# M_I_ext_sound_usb.net
KiCad netlist of a schematic drawn in EAGLE
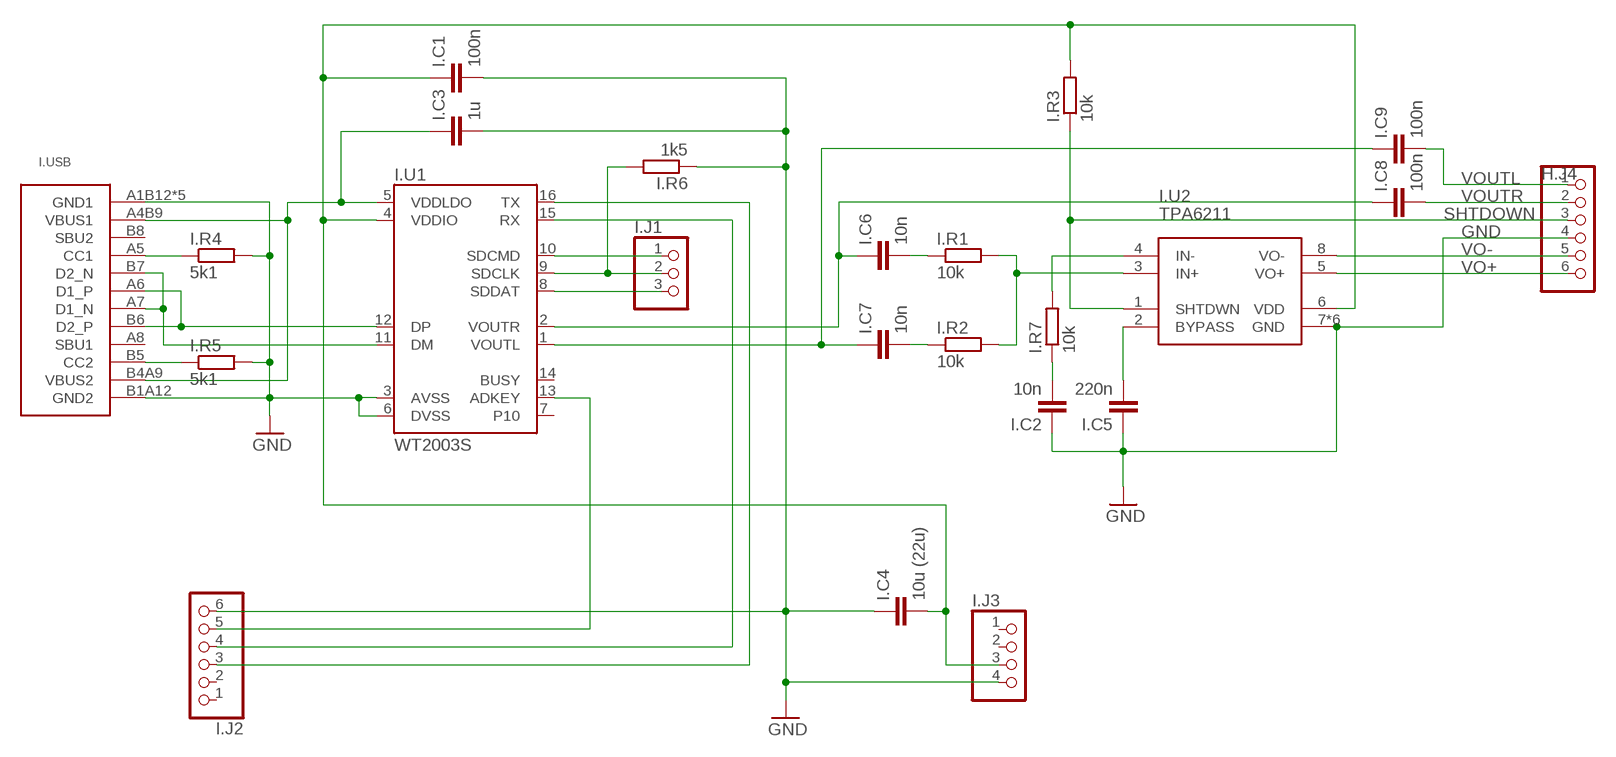
[diagram p0: schematic, sheet 1]

(export (version "E")
  (design (tool "Eeschema 10.0.6"))
  (components
    (comp (ref "H.J4")
      (value "PINHD-1X6")
      (footprint "eagle-import:1X06")
      (libsource (lib "eagle-import") (part "PINHD-1X6"))
    )
    (comp (ref "I.C1")
      (value "100n")
      (footprint "eagle-import:C0603")
      (libsource (lib "eagle-import") (part "C-EUC0603"))
    )
    (comp (ref "I.C2")
      (value "10n")
      (footprint "eagle-import:C0603")
      (libsource (lib "eagle-import") (part "C-EUC0603"))
    )
    (comp (ref "I.C3")
      (value "1u")
      (footprint "eagle-import:C0603")
      (libsource (lib "eagle-import") (part "C-EUC0603"))
    )
    (comp (ref "I.C4")
      (value "10u (22u)")
      (footprint "eagle-import:C0805")
      (libsource (lib "eagle-import") (part "C-EUC0805"))
    )
    (comp (ref "I.C5")
      (value "220n")
      (footprint "eagle-import:C0603")
      (libsource (lib "eagle-import") (part "C-EUC0603"))
    )
    (comp (ref "I.C6")
      (value "10n")
      (footprint "eagle-import:C0603")
      (libsource (lib "eagle-import") (part "C-EUC0603"))
    )
    (comp (ref "I.C7")
      (value "10n")
      (footprint "eagle-import:C0603")
      (libsource (lib "eagle-import") (part "C-EUC0603"))
    )
    (comp (ref "I.C8")
      (value "100n")
      (footprint "eagle-import:C0603")
      (libsource (lib "eagle-import") (part "C-EUC0603"))
    )
    (comp (ref "I.C9")
      (value "100n")
      (footprint "eagle-import:C0603")
      (libsource (lib "eagle-import") (part "C-EUC0603"))
    )
    (comp (ref "I.J1")
      (value "PINHD-1X3")
      (footprint "eagle-import:1X03")
      (libsource (lib "eagle-import") (part "PINHD-1X3"))
    )
    (comp (ref "I.J2")
      (value "PINHD-1X6")
      (footprint "eagle-import:1X06")
      (libsource (lib "eagle-import") (part "PINHD-1X6"))
    )
    (comp (ref "I.J3")
      (value "PINHD-1X4")
      (footprint "eagle-import:1X04")
      (libsource (lib "eagle-import") (part "PINHD-1X4"))
    )
    (comp (ref "I.R1")
      (value "10k")
      (footprint "eagle-import:R0603")
      (libsource (lib "eagle-import") (part "R-EU_R0603"))
    )
    (comp (ref "I.R2")
      (value "10k")
      (footprint "eagle-import:R0603")
      (libsource (lib "eagle-import") (part "R-EU_R0603"))
    )
    (comp (ref "I.R3")
      (value "10k")
      (footprint "eagle-import:R0603")
      (libsource (lib "eagle-import") (part "R-EU_R0603"))
    )
    (comp (ref "I.R4")
      (value "5k1")
      (footprint "eagle-import:R0603")
      (libsource (lib "eagle-import") (part "R-EU_R0603"))
    )
    (comp (ref "I.R5")
      (value "5k1")
      (footprint "eagle-import:R0603")
      (libsource (lib "eagle-import") (part "R-EU_R0603"))
    )
    (comp (ref "I.R6")
      (value "1k5")
      (footprint "eagle-import:R0603")
      (libsource (lib "eagle-import") (part "R-EU_R0603"))
    )
    (comp (ref "I.R7")
      (value "10k")
      (footprint "eagle-import:R0603")
      (libsource (lib "eagle-import") (part "R-EU_R0603"))
    )
    (comp (ref "I.U1")
      (value "WT2003S")
      (footprint "eagle-import:SO16")
      (libsource (lib "eagle-import") (part "WT2003S"))
    )
    (comp (ref "I.U2")
      (value "TPA6211")
      (footprint "eagle-import:MSOP-POWERPAD-8")
      (libsource (lib "eagle-import") (part "TPA6211"))
    )
    (comp (ref "I.USB")
      (value "USB-C")
      (footprint "eagle-import:USB-C")
      (libsource (lib "eagle-import") (part "USB-C"))
    )
  )
  (nets
    (net (code "1") (name "/SHTDOWN") (class "Default")
      (node (ref "H.J4") (pin "3") (pinfunction "3_3") (pintype "passive"))
      (node (ref "I.R3") (pin "1") (pinfunction "1_1") (pintype "passive"))
      (node (ref "I.U2") (pin "1") (pinfunction "SHTDWN_1") (pintype "bidirectional"))
    )
    (net (code "2") (name "/VO+") (class "Default")
      (node (ref "H.J4") (pin "6") (pinfunction "6_6") (pintype "passive"))
      (node (ref "I.U2") (pin "5") (pinfunction "VO+_5") (pintype "bidirectional"))
    )
    (net (code "3") (name "/VO-") (class "Default")
      (node (ref "H.J4") (pin "5") (pinfunction "5_5") (pintype "passive"))
      (node (ref "I.U2") (pin "8") (pinfunction "VO-_8") (pintype "bidirectional"))
    )
    (net (code "4") (name "/VOUTL") (class "Default")
      (node (ref "H.J4") (pin "1") (pinfunction "1_1") (pintype "passive"))
      (node (ref "I.C9") (pin "2") (pinfunction "2_2") (pintype "passive"))
    )
    (net (code "5") (name "/VOUTR") (class "Default")
      (node (ref "H.J4") (pin "2") (pinfunction "2_2") (pintype "passive"))
      (node (ref "I.C8") (pin "2") (pinfunction "2_2") (pintype "passive"))
    )
    (net (code "6") (name "GND") (class "Default")
      (node (ref "H.J4") (pin "4") (pinfunction "4_4") (pintype "passive"))
      (node (ref "I.C1") (pin "2") (pinfunction "2_2") (pintype "passive"))
      (node (ref "I.C2") (pin "1") (pinfunction "1_1") (pintype "passive"))
      (node (ref "I.C3") (pin "2") (pinfunction "2_2") (pintype "passive"))
      (node (ref "I.C4") (pin "1") (pinfunction "1_1") (pintype "passive"))
      (node (ref "I.C5") (pin "1") (pinfunction "1_1") (pintype "passive"))
      (node (ref "I.J2") (pin "6") (pinfunction "6_6") (pintype "passive"))
      (node (ref "I.J3") (pin "4") (pinfunction "4_4") (pintype "passive"))
      (node (ref "I.R4") (pin "2") (pinfunction "2_2") (pintype "passive"))
      (node (ref "I.R5") (pin "2") (pinfunction "2_2") (pintype "passive"))
      (node (ref "I.R6") (pin "1") (pinfunction "1_1") (pintype "passive"))
      (node (ref "I.U1") (pin "3") (pinfunction "AVSS_3") (pintype "bidirectional"))
      (node (ref "I.U1") (pin "6") (pinfunction "DVSS_6") (pintype "bidirectional"))
      (node (ref "I.U2") (pin "7") (pinfunction "GND_7") (pintype "bidirectional"))
      (node (ref "I.U2") (pin "9") (pinfunction "GND_9") (pintype "bidirectional"))
      (node (ref "I.U2") (pin "P$10") (pinfunction "GND_P$10") (pintype "bidirectional"))
      (node (ref "I.U2") (pin "P$11") (pinfunction "GND_P$11") (pintype "bidirectional"))
      (node (ref "I.U2") (pin "P$12") (pinfunction "GND_P$12") (pintype "bidirectional"))
      (node (ref "I.U2") (pin "P$13") (pinfunction "GND_P$13") (pintype "bidirectional"))
      (node (ref "I.USB") (pin "A1B12") (pinfunction "GND1_A1B12") (pintype "bidirectional"))
      (node (ref "I.USB") (pin "B1A12") (pinfunction "GND2_B1A12") (pintype "bidirectional"))
      (node (ref "I.USB") (pin "SH1") (pinfunction "GND1_SH1") (pintype "bidirectional"))
      (node (ref "I.USB") (pin "SH2") (pinfunction "GND1_SH2") (pintype "bidirectional"))
      (node (ref "I.USB") (pin "SH3") (pinfunction "GND1_SH3") (pintype "bidirectional"))
      (node (ref "I.USB") (pin "SH4") (pinfunction "GND1_SH4") (pintype "bidirectional"))
    )
    (net (code "7") (name "Net-(I.C2-Pad2)") (class "Default")
      (node (ref "I.C2") (pin "2") (pinfunction "2_2") (pintype "passive"))
      (node (ref "I.R7") (pin "1") (pinfunction "1_1") (pintype "passive"))
    )
    (net (code "8") (name "Net-(I.C6-Pad2)") (class "Default")
      (node (ref "I.C6") (pin "2") (pinfunction "2_2") (pintype "passive"))
      (node (ref "I.R1") (pin "1") (pinfunction "1_1") (pintype "passive"))
    )
    (net (code "9") (name "Net-(I.C7-Pad2)") (class "Default")
      (node (ref "I.C7") (pin "2") (pinfunction "2_2") (pintype "passive"))
      (node (ref "I.R2") (pin "1") (pinfunction "1_1") (pintype "passive"))
    )
    (net (code "10") (name "Net-(I.U1-ADKEY)") (class "Default")
      (node (ref "I.J2") (pin "5") (pinfunction "5_5") (pintype "passive"))
      (node (ref "I.U1") (pin "13") (pinfunction "ADKEY_13") (pintype "bidirectional"))
    )
    (net (code "11") (name "Net-(I.U1-DM)") (class "Default")
      (node (ref "I.U1") (pin "11") (pinfunction "DM_11") (pintype "bidirectional"))
      (node (ref "I.USB") (pin "A7") (pinfunction "D1_N_A7") (pintype "bidirectional"))
      (node (ref "I.USB") (pin "B7") (pinfunction "D2_N_B7") (pintype "bidirectional"))
    )
    (net (code "12") (name "Net-(I.U1-DP)") (class "Default")
      (node (ref "I.U1") (pin "12") (pinfunction "DP_12") (pintype "bidirectional"))
      (node (ref "I.USB") (pin "A6") (pinfunction "D1_P_A6") (pintype "bidirectional"))
      (node (ref "I.USB") (pin "B6") (pinfunction "D2_P_B6") (pintype "bidirectional"))
    )
    (net (code "13") (name "Net-(I.U1-RX)") (class "Default")
      (node (ref "I.J2") (pin "4") (pinfunction "4_4") (pintype "passive"))
      (node (ref "I.U1") (pin "15") (pinfunction "RX_15") (pintype "bidirectional"))
    )
    (net (code "14") (name "Net-(I.U1-SDCLK)") (class "Default")
      (node (ref "I.J1") (pin "2") (pinfunction "2_2") (pintype "passive"))
      (node (ref "I.R6") (pin "2") (pinfunction "2_2") (pintype "passive"))
      (node (ref "I.U1") (pin "9") (pinfunction "SDCLK_9") (pintype "bidirectional"))
    )
    (net (code "15") (name "Net-(I.U1-SDCMD)") (class "Default")
      (node (ref "I.J1") (pin "1") (pinfunction "1_1") (pintype "passive"))
      (node (ref "I.U1") (pin "10") (pinfunction "SDCMD_10") (pintype "bidirectional"))
    )
    (net (code "16") (name "Net-(I.U1-SDDAT)") (class "Default")
      (node (ref "I.J1") (pin "3") (pinfunction "3_3") (pintype "passive"))
      (node (ref "I.U1") (pin "8") (pinfunction "SDDAT_8") (pintype "bidirectional"))
    )
    (net (code "17") (name "Net-(I.U1-TX)") (class "Default")
      (node (ref "I.J2") (pin "3") (pinfunction "3_3") (pintype "passive"))
      (node (ref "I.U1") (pin "16") (pinfunction "TX_16") (pintype "bidirectional"))
    )
    (net (code "18") (name "Net-(I.U1-VDDIO)") (class "Default")
      (node (ref "I.C1") (pin "1") (pinfunction "1_1") (pintype "passive"))
      (node (ref "I.C4") (pin "2") (pinfunction "2_2") (pintype "passive"))
      (node (ref "I.J3") (pin "3") (pinfunction "3_3") (pintype "passive"))
      (node (ref "I.R3") (pin "2") (pinfunction "2_2") (pintype "passive"))
      (node (ref "I.U1") (pin "4") (pinfunction "VDDIO_4") (pintype "bidirectional"))
      (node (ref "I.U2") (pin "6") (pinfunction "VDD_6") (pintype "bidirectional"))
    )
    (net (code "19") (name "Net-(I.U1-VDDLDO)") (class "Default")
      (node (ref "I.C3") (pin "1") (pinfunction "1_1") (pintype "passive"))
      (node (ref "I.U1") (pin "5") (pinfunction "VDDLDO_5") (pintype "bidirectional"))
      (node (ref "I.USB") (pin "A4B9") (pinfunction "VBUS1_A4B9") (pintype "bidirectional"))
      (node (ref "I.USB") (pin "B4A9") (pinfunction "VBUS2_B4A9") (pintype "bidirectional"))
    )
    (net (code "20") (name "Net-(I.U1-VOUTL)") (class "Default")
      (node (ref "I.C7") (pin "1") (pinfunction "1_1") (pintype "passive"))
      (node (ref "I.C9") (pin "1") (pinfunction "1_1") (pintype "passive"))
      (node (ref "I.U1") (pin "1") (pinfunction "VOUTL_1") (pintype "bidirectional"))
    )
    (net (code "21") (name "Net-(I.U1-VOUTR)") (class "Default")
      (node (ref "I.C6") (pin "1") (pinfunction "1_1") (pintype "passive"))
      (node (ref "I.C8") (pin "1") (pinfunction "1_1") (pintype "passive"))
      (node (ref "I.U1") (pin "2") (pinfunction "VOUTR_2") (pintype "bidirectional"))
    )
    (net (code "22") (name "Net-(I.U2-BYPASS)") (class "Default")
      (node (ref "I.C5") (pin "2") (pinfunction "2_2") (pintype "passive"))
      (node (ref "I.U2") (pin "2") (pinfunction "BYPASS_2") (pintype "bidirectional"))
    )
    (net (code "23") (name "Net-(I.U2-IN+)") (class "Default")
      (node (ref "I.R1") (pin "2") (pinfunction "2_2") (pintype "passive"))
      (node (ref "I.R2") (pin "2") (pinfunction "2_2") (pintype "passive"))
      (node (ref "I.U2") (pin "3") (pinfunction "IN+_3") (pintype "bidirectional"))
    )
    (net (code "24") (name "Net-(I.U2-IN-)") (class "Default")
      (node (ref "I.R7") (pin "2") (pinfunction "2_2") (pintype "passive"))
      (node (ref "I.U2") (pin "4") (pinfunction "IN-_4") (pintype "bidirectional"))
    )
    (net (code "25") (name "Net-(I.USB-CC1)") (class "Default")
      (node (ref "I.R4") (pin "1") (pinfunction "1_1") (pintype "passive"))
      (node (ref "I.USB") (pin "A5") (pinfunction "CC1_A5") (pintype "bidirectional"))
    )
    (net (code "26") (name "Net-(I.USB-CC2)") (class "Default")
      (node (ref "I.R5") (pin "1") (pinfunction "1_1") (pintype "passive"))
      (node (ref "I.USB") (pin "B5") (pinfunction "CC2_B5") (pintype "bidirectional"))
    )
    (net (code "27") (name "unconnected-(I.J2-Pad1)") (class "Default")
      (node (ref "I.J2") (pin "1") (pinfunction "1_1") (pintype "passive"))
    )
    (net (code "28") (name "unconnected-(I.J2-Pad2)") (class "Default")
      (node (ref "I.J2") (pin "2") (pinfunction "2_2") (pintype "passive"))
    )
    (net (code "29") (name "unconnected-(I.J3-Pad1)") (class "Default")
      (node (ref "I.J3") (pin "1") (pinfunction "1_1") (pintype "passive"))
    )
    (net (code "30") (name "unconnected-(I.J3-Pad2)") (class "Default")
      (node (ref "I.J3") (pin "2") (pinfunction "2_2") (pintype "passive"))
    )
    (net (code "31") (name "unconnected-(I.U1-BUSY-Pad14)") (class "Default")
      (node (ref "I.U1") (pin "14") (pinfunction "BUSY_14") (pintype "bidirectional"))
    )
    (net (code "32") (name "unconnected-(I.U1-P10-Pad7)") (class "Default")
      (node (ref "I.U1") (pin "7") (pinfunction "P10_7") (pintype "bidirectional"))
    )
    (net (code "33") (name "unconnected-(I.USB-SBU1-PadA8)") (class "Default")
      (node (ref "I.USB") (pin "A8") (pinfunction "SBU1_A8") (pintype "bidirectional"))
    )
    (net (code "34") (name "unconnected-(I.USB-SBU2-PadB8)") (class "Default")
      (node (ref "I.USB") (pin "B8") (pinfunction "SBU2_B8") (pintype "bidirectional"))
    )
  )
)
